# design.net
KiCad netlist of a schematic drawn in Altium Designer
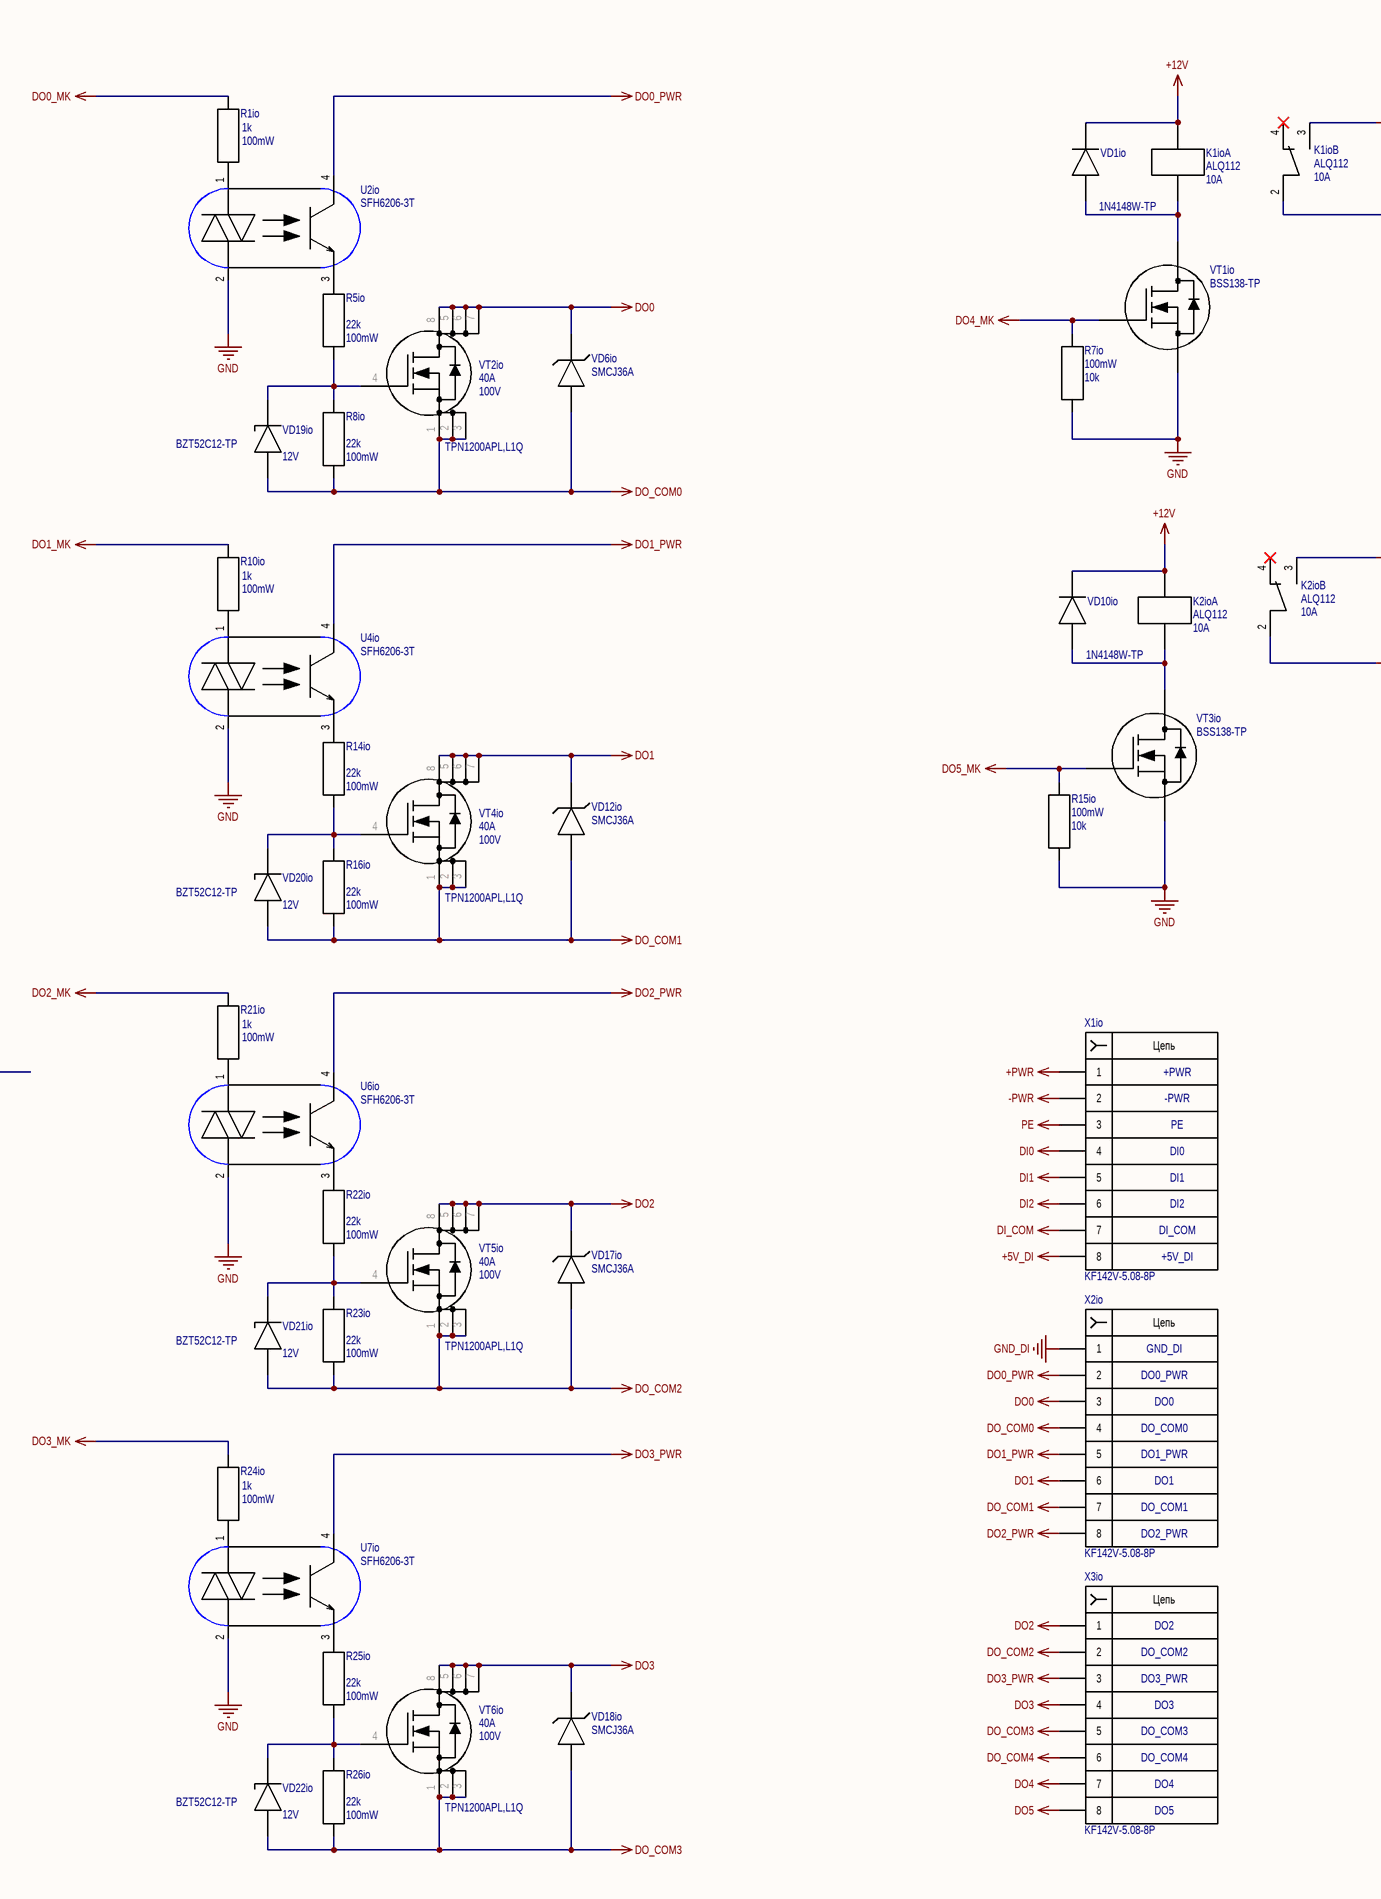
[diagram p0: Схема дискретных входов и выходов.SchDoc, left]
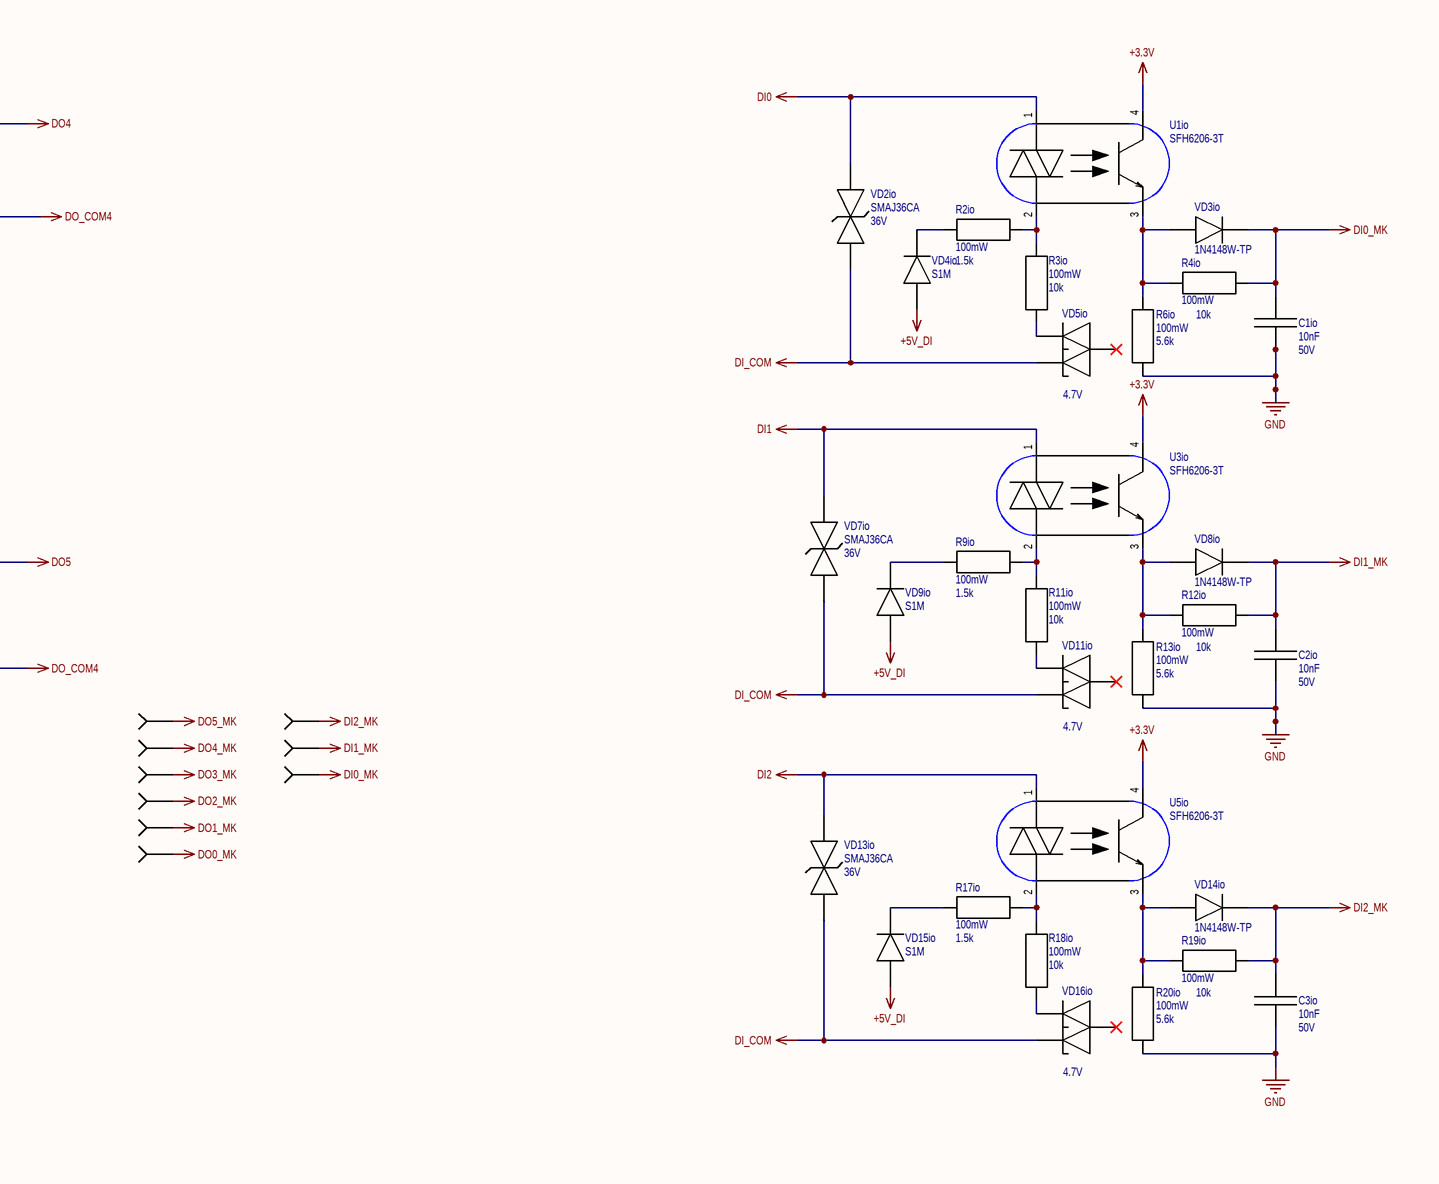
[diagram p1: Схема дискретных входов и выходов.SchDoc, right]

(export (version "E")
  (design (tool "Eeschema 10.0.6"))
  (components
    (comp (ref "C1io")
      (value "CL10B103KB8NNNC")
      (footprint "CAP 0603 IPC MAX")
      (description "CAP SMD CER 10000PF 50V X7R 0603")
      (fields
        (field (name "TOLERANCE") "10%")
        (field (name "CAPACITANCE") "10nF")
        (field (name "RATED VOLTAGE") "50V")
      )
      (libsource (lib "Passive components") (part "CL10B103KB8NNNC"))
    )
    (comp (ref "C2io")
      (value "CL10B103KB8NNNC")
      (footprint "CAP 0603 IPC MAX")
      (description "CAP SMD CER 10000PF 50V X7R 0603")
      (fields
        (field (name "TOLERANCE") "10%")
        (field (name "CAPACITANCE") "10nF")
        (field (name "RATED VOLTAGE") "50V")
      )
      (libsource (lib "Passive components") (part "CL10B103KB8NNNC"))
    )
    (comp (ref "C3io")
      (value "CL10B103KB8NNNC")
      (footprint "CAP 0603 IPC MAX")
      (description "CAP SMD CER 10000PF 50V X7R 0603")
      (fields
        (field (name "TOLERANCE") "10%")
        (field (name "CAPACITANCE") "10nF")
        (field (name "RATED VOLTAGE") "50V")
      )
      (libsource (lib "Passive components") (part "CL10B103KB8NNNC"))
    )
    (comp (ref "K1io")
      (value "ALQ112")
      (footprint "ALQ112")
      (description "RELAY GEN PURPOSE SPDT 10A 12V")
      (fields (field (name "CONTACT RATING") "10A"))
      (libsource (lib "Electromechanical") (part "ALQ112"))
    )
    (comp (ref "K2io")
      (value "ALQ112")
      (footprint "ALQ112")
      (description "RELAY GEN PURPOSE SPDT 10A 12V")
      (fields (field (name "CONTACT RATING") "10A"))
      (libsource (lib "Electromechanical") (part "ALQ112"))
    )
    (comp (ref "R1io")
      (value "RMCF0603FT1K00")
      (footprint "RES 0603 IPC MAX")
      (description "RES SMD 1K OHM 1% 1/10W 0603")
      (fields
        (field (name "RESISTANCE") "1k")
        (field (name "TOLERANCE") "1%")
        (field (name "RATED POWER") "100mW")
      )
      (libsource (lib "Passive components") (part "RMCF0603FT1K00"))
    )
    (comp (ref "R2io")
      (value "RMCF0603FT1K50")
      (footprint "CAP 0603 IPC MAX")
      (description "RES SMD 1.5K OHM 1% 1/10W 0603")
      (fields
        (field (name "TOLERANCE") "1%")
        (field (name "POWER RATED") "100mW")
        (field (name "RESISTANCE") "1.5k")
      )
      (libsource (lib "Passive components") (part "RMCF0603FT1K50"))
    )
    (comp (ref "R3io")
      (value "RMCF0603JT10K0")
      (footprint "RES 0603 IPC MAX")
      (description "RES SMD 10K OHM 5% 1/10W 0603")
      (fields
        (field (name "TOLERANCE") "5%")
        (field (name "POWER RATED") "100mW")
        (field (name "RESISTANCE") "10k")
      )
      (libsource (lib "Passive components") (part "RMCF0603JT10K0"))
    )
    (comp (ref "R4io")
      (value "RMCF0603JT10K0")
      (footprint "RES 0603 IPC MAX")
      (description "RES SMD 10K OHM 5% 1/10W 0603")
      (fields
        (field (name "TOLERANCE") "5%")
        (field (name "POWER RATED") "100mW")
        (field (name "RESISTANCE") "10k")
      )
      (libsource (lib "Passive components") (part "RMCF0603JT10K0"))
    )
    (comp (ref "R5io")
      (value "RMCF0603FT22K0")
      (footprint "RES 0603 IPC MAX")
      (description "RES SMD 22K OHM 1% 1/10W 0603")
      (fields
        (field (name "TOLERANCE") "1%")
        (field (name "RESISTANCE") "22k")
        (field (name "POWER RATED") "100mW")
      )
      (libsource (lib "Passive components") (part "RMCF0603FT22K0"))
    )
    (comp (ref "R6io")
      (value "RMCF0603FT5K60")
      (footprint "RES 0603 IPC MAX")
      (description "RES SMD 5.6K OHM 1% 1/10W 0603")
      (fields
        (field (name "RESISTANCE") "5.6k")
        (field (name "TOLERANCE") "1%")
        (field (name "RATED POWER") "100mW")
      )
      (libsource (lib "Passive components") (part "RMCF0603FT5K60"))
    )
    (comp (ref "R7io")
      (value "RMCF0603JT10K0")
      (footprint "RES 0603 IPC MAX")
      (description "RES SMD 10K OHM 5% 1/10W 0603")
      (fields
        (field (name "TOLERANCE") "5%")
        (field (name "POWER RATED") "100mW")
        (field (name "RESISTANCE") "10k")
      )
      (libsource (lib "Passive components") (part "RMCF0603JT10K0"))
    )
    (comp (ref "R8io")
      (value "RMCF0603FT22K0")
      (footprint "RES 0603 IPC MAX")
      (description "RES SMD 22K OHM 1% 1/10W 0603")
      (fields
        (field (name "TOLERANCE") "1%")
        (field (name "RESISTANCE") "22k")
        (field (name "POWER RATED") "100mW")
      )
      (libsource (lib "Passive components") (part "RMCF0603FT22K0"))
    )
    (comp (ref "R9io")
      (value "RMCF0603FT1K50")
      (footprint "CAP 0603 IPC MAX")
      (description "RES SMD 1.5K OHM 1% 1/10W 0603")
      (fields
        (field (name "TOLERANCE") "1%")
        (field (name "POWER RATED") "100mW")
        (field (name "RESISTANCE") "1.5k")
      )
      (libsource (lib "Passive components") (part "RMCF0603FT1K50"))
    )
    (comp (ref "R10io")
      (value "RMCF0603FT1K00")
      (footprint "RES 0603 IPC MAX")
      (description "RES SMD 1K OHM 1% 1/10W 0603")
      (fields
        (field (name "RESISTANCE") "1k")
        (field (name "TOLERANCE") "1%")
        (field (name "RATED POWER") "100mW")
      )
      (libsource (lib "Passive components") (part "RMCF0603FT1K00"))
    )
    (comp (ref "R11io")
      (value "RMCF0603JT10K0")
      (footprint "RES 0603 IPC MAX")
      (description "RES SMD 10K OHM 5% 1/10W 0603")
      (fields
        (field (name "TOLERANCE") "5%")
        (field (name "POWER RATED") "100mW")
        (field (name "RESISTANCE") "10k")
      )
      (libsource (lib "Passive components") (part "RMCF0603JT10K0"))
    )
    (comp (ref "R12io")
      (value "RMCF0603JT10K0")
      (footprint "RES 0603 IPC MAX")
      (description "RES SMD 10K OHM 5% 1/10W 0603")
      (fields
        (field (name "TOLERANCE") "5%")
        (field (name "POWER RATED") "100mW")
        (field (name "RESISTANCE") "10k")
      )
      (libsource (lib "Passive components") (part "RMCF0603JT10K0"))
    )
    (comp (ref "R13io")
      (value "RMCF0603FT5K60")
      (footprint "RES 0603 IPC MAX")
      (description "RES SMD 5.6K OHM 1% 1/10W 0603")
      (fields
        (field (name "RESISTANCE") "5.6k")
        (field (name "TOLERANCE") "1%")
        (field (name "RATED POWER") "100mW")
      )
      (libsource (lib "Passive components") (part "RMCF0603FT5K60"))
    )
    (comp (ref "R14io")
      (value "RMCF0603FT22K0")
      (footprint "RES 0603 IPC MAX")
      (description "RES SMD 22K OHM 1% 1/10W 0603")
      (fields
        (field (name "TOLERANCE") "1%")
        (field (name "RESISTANCE") "22k")
        (field (name "POWER RATED") "100mW")
      )
      (libsource (lib "Passive components") (part "RMCF0603FT22K0"))
    )
    (comp (ref "R15io")
      (value "RMCF0603JT10K0")
      (footprint "RES 0603 IPC MAX")
      (description "RES SMD 10K OHM 5% 1/10W 0603")
      (fields
        (field (name "TOLERANCE") "5%")
        (field (name "POWER RATED") "100mW")
        (field (name "RESISTANCE") "10k")
      )
      (libsource (lib "Passive components") (part "RMCF0603JT10K0"))
    )
    (comp (ref "R16io")
      (value "RMCF0603FT22K0")
      (footprint "RES 0603 IPC MAX")
      (description "RES SMD 22K OHM 1% 1/10W 0603")
      (fields
        (field (name "TOLERANCE") "1%")
        (field (name "RESISTANCE") "22k")
        (field (name "POWER RATED") "100mW")
      )
      (libsource (lib "Passive components") (part "RMCF0603FT22K0"))
    )
    (comp (ref "R17io")
      (value "RMCF0603FT1K50")
      (footprint "CAP 0603 IPC MAX")
      (description "RES SMD 1.5K OHM 1% 1/10W 0603")
      (fields
        (field (name "TOLERANCE") "1%")
        (field (name "POWER RATED") "100mW")
        (field (name "RESISTANCE") "1.5k")
      )
      (libsource (lib "Passive components") (part "RMCF0603FT1K50"))
    )
    (comp (ref "R18io")
      (value "RMCF0603JT10K0")
      (footprint "RES 0603 IPC MAX")
      (description "RES SMD 10K OHM 5% 1/10W 0603")
      (fields
        (field (name "TOLERANCE") "5%")
        (field (name "POWER RATED") "100mW")
        (field (name "RESISTANCE") "10k")
      )
      (libsource (lib "Passive components") (part "RMCF0603JT10K0"))
    )
    (comp (ref "R19io")
      (value "RMCF0603JT10K0")
      (footprint "RES 0603 IPC MAX")
      (description "RES SMD 10K OHM 5% 1/10W 0603")
      (fields
        (field (name "TOLERANCE") "5%")
        (field (name "POWER RATED") "100mW")
        (field (name "RESISTANCE") "10k")
      )
      (libsource (lib "Passive components") (part "RMCF0603JT10K0"))
    )
    (comp (ref "R20io")
      (value "RMCF0603FT5K60")
      (footprint "RES 0603 IPC MAX")
      (description "RES SMD 5.6K OHM 1% 1/10W 0603")
      (fields
        (field (name "RESISTANCE") "5.6k")
        (field (name "TOLERANCE") "1%")
        (field (name "RATED POWER") "100mW")
      )
      (libsource (lib "Passive components") (part "RMCF0603FT5K60"))
    )
    (comp (ref "R21io")
      (value "RMCF0603FT1K00")
      (footprint "RES 0603 IPC MAX")
      (description "RES SMD 1K OHM 1% 1/10W 0603")
      (fields
        (field (name "RESISTANCE") "1k")
        (field (name "TOLERANCE") "1%")
        (field (name "RATED POWER") "100mW")
      )
      (libsource (lib "Passive components") (part "RMCF0603FT1K00"))
    )
    (comp (ref "R22io")
      (value "RMCF0603FT22K0")
      (footprint "RES 0603 IPC MAX")
      (description "RES SMD 22K OHM 1% 1/10W 0603")
      (fields
        (field (name "TOLERANCE") "1%")
        (field (name "RESISTANCE") "22k")
        (field (name "POWER RATED") "100mW")
      )
      (libsource (lib "Passive components") (part "RMCF0603FT22K0"))
    )
    (comp (ref "R23io")
      (value "RMCF0603FT22K0")
      (footprint "RES 0603 IPC MAX")
      (description "RES SMD 22K OHM 1% 1/10W 0603")
      (fields
        (field (name "TOLERANCE") "1%")
        (field (name "RESISTANCE") "22k")
        (field (name "POWER RATED") "100mW")
      )
      (libsource (lib "Passive components") (part "RMCF0603FT22K0"))
    )
    (comp (ref "R24io")
      (value "RMCF0603FT1K00")
      (footprint "RES 0603 IPC MAX")
      (description "RES SMD 1K OHM 1% 1/10W 0603")
      (fields
        (field (name "RESISTANCE") "1k")
        (field (name "TOLERANCE") "1%")
        (field (name "RATED POWER") "100mW")
      )
      (libsource (lib "Passive components") (part "RMCF0603FT1K00"))
    )
    (comp (ref "R25io")
      (value "RMCF0603FT22K0")
      (footprint "RES 0603 IPC MAX")
      (description "RES SMD 22K OHM 1% 1/10W 0603")
      (fields
        (field (name "TOLERANCE") "1%")
        (field (name "RESISTANCE") "22k")
        (field (name "POWER RATED") "100mW")
      )
      (libsource (lib "Passive components") (part "RMCF0603FT22K0"))
    )
    (comp (ref "R26io")
      (value "RMCF0603FT22K0")
      (footprint "RES 0603 IPC MAX")
      (description "RES SMD 22K OHM 1% 1/10W 0603")
      (fields
        (field (name "TOLERANCE") "1%")
        (field (name "RESISTANCE") "22k")
        (field (name "POWER RATED") "100mW")
      )
      (libsource (lib "Passive components") (part "RMCF0603FT22K0"))
    )
    (comp (ref "TP1io")
      (value "1.2MM TP")
      (footprint "TESTPOINT 1.2mm")
      (libsource (lib "Connectors") (part "Testpoint 1.2mm"))
    )
    (comp (ref "TP2io")
      (value "1.2MM TP")
      (footprint "TESTPOINT 1.2mm")
      (libsource (lib "Connectors") (part "Testpoint 1.2mm"))
    )
    (comp (ref "TP3io")
      (value "1.2MM TP")
      (footprint "TESTPOINT 1.2mm")
      (libsource (lib "Connectors") (part "Testpoint 1.2mm"))
    )
    (comp (ref "TP4io")
      (value "1.2MM TP")
      (footprint "TESTPOINT 1.2mm")
      (libsource (lib "Connectors") (part "Testpoint 1.2mm"))
    )
    (comp (ref "TP5io")
      (value "1.2MM TP")
      (footprint "TESTPOINT 1.2mm")
      (libsource (lib "Connectors") (part "Testpoint 1.2mm"))
    )
    (comp (ref "TP6io")
      (value "1.2MM TP")
      (footprint "TESTPOINT 1.2mm")
      (libsource (lib "Connectors") (part "Testpoint 1.2mm"))
    )
    (comp (ref "TP7io")
      (value "1.2MM TP")
      (footprint "TESTPOINT 1.2mm")
      (libsource (lib "Connectors") (part "Testpoint 1.2mm"))
    )
    (comp (ref "TP9io")
      (value "1.2MM TP")
      (footprint "TESTPOINT 1.2mm")
      (libsource (lib "Connectors") (part "Testpoint 1.2mm"))
    )
    (comp (ref "TP11io")
      (value "1.2MM TP")
      (footprint "TESTPOINT 1.2mm")
      (libsource (lib "Connectors") (part "Testpoint 1.2mm"))
    )
    (comp (ref "U1io")
      (value "SFH6206-3T")
      (footprint "11-5L106")
      (description "OPTOISOLATOR 5.3KV TRANS 4-SMD")
      (libsource (lib "Optos") (part "SFH6206-3T"))
    )
    (comp (ref "U2io")
      (value "SFH6206-3T")
      (footprint "11-5L106")
      (description "OPTOISOLATOR 5.3KV TRANS 4-SMD")
      (libsource (lib "Optos") (part "SFH6206-3T"))
    )
    (comp (ref "U3io")
      (value "SFH6206-3T")
      (footprint "11-5L106")
      (description "OPTOISOLATOR 5.3KV TRANS 4-SMD")
      (libsource (lib "Optos") (part "SFH6206-3T"))
    )
    (comp (ref "U4io")
      (value "SFH6206-3T")
      (footprint "11-5L106")
      (description "OPTOISOLATOR 5.3KV TRANS 4-SMD")
      (libsource (lib "Optos") (part "SFH6206-3T"))
    )
    (comp (ref "U5io")
      (value "SFH6206-3T")
      (footprint "11-5L106")
      (description "OPTOISOLATOR 5.3KV TRANS 4-SMD")
      (libsource (lib "Optos") (part "SFH6206-3T"))
    )
    (comp (ref "U6io")
      (value "SFH6206-3T")
      (footprint "11-5L106")
      (description "OPTOISOLATOR 5.3KV TRANS 4-SMD")
      (libsource (lib "Optos") (part "SFH6206-3T"))
    )
    (comp (ref "U7io")
      (value "SFH6206-3T")
      (footprint "11-5L106")
      (description "OPTOISOLATOR 5.3KV TRANS 4-SMD")
      (libsource (lib "Optos") (part "SFH6206-3T"))
    )
    (comp (ref "VD1io")
      (value "1N4148W-TP")
      (footprint "SOD-123 (Marked)")
      (description "DIODE GEN PURP 100V 150MA SOD123")
      (libsource (lib "Diodes") (part "1N4148W-TP"))
    )
    (comp (ref "VD2io")
      (value "SMAJ36CA")
      (footprint "DO-214AC Bidirectional")
      (description "TVS DIODE 36VWM 58.1VC DO214AC")
      (fields (field (name "VOLTAGE - REVERSE STANDOFF (TYP)") "36V"))
      (libsource (lib "Diodes") (part "SMAJ36CA"))
    )
    (comp (ref "VD3io")
      (value "1N4148W-TP")
      (footprint "SOD-123 (Marked)")
      (description "DIODE GEN PURP 100V 150MA SOD123")
      (libsource (lib "Diodes") (part "1N4148W-TP"))
    )
    (comp (ref "VD4io")
      (value "S1M")
      (footprint "DO-214AC Unidirectional")
      (description "DIODE GEN PURP 1KV 1A SMA")
      (libsource (lib "Diodes") (part "S1M"))
    )
    (comp (ref "VD5io")
      (value "AZ23C4V7-HE3-08")
      (footprint "SOT-23-3")
      (description "DIODE ZENER ARRAY 4.7V 300MW SOT23")
      (fields (field (name "ZENER VOLTAGE") "4.7V") (field (name "TOLERANCE") "5%"))
      (libsource (lib "Diodes") (part "AZ23C4V7-HE3-08"))
    )
    (comp (ref "VD6io")
      (value "SMCJ36A")
      (footprint "DO214-AB (SMC) L3.2W1.52")
      (description "TVS DIODE 36VWM 58.1VC DO214AB")
      (libsource (lib "Diodes") (part "SMCJ36A"))
    )
    (comp (ref "VD7io")
      (value "SMAJ36CA")
      (footprint "DO-214AC Bidirectional")
      (description "TVS DIODE 36VWM 58.1VC DO214AC")
      (fields (field (name "VOLTAGE - REVERSE STANDOFF (TYP)") "36V"))
      (libsource (lib "Diodes") (part "SMAJ36CA"))
    )
    (comp (ref "VD8io")
      (value "1N4148W-TP")
      (footprint "SOD-123 (Marked)")
      (description "DIODE GEN PURP 100V 150MA SOD123")
      (libsource (lib "Diodes") (part "1N4148W-TP"))
    )
    (comp (ref "VD9io")
      (value "S1M")
      (footprint "DO-214AC Unidirectional")
      (description "DIODE GEN PURP 1KV 1A SMA")
      (libsource (lib "Diodes") (part "S1M"))
    )
    (comp (ref "VD10io")
      (value "1N4148W-TP")
      (footprint "SOD-123 (Marked)")
      (description "DIODE GEN PURP 100V 150MA SOD123")
      (libsource (lib "Diodes") (part "1N4148W-TP"))
    )
    (comp (ref "VD11io")
      (value "AZ23C4V7-HE3-08")
      (footprint "SOT-23-3")
      (description "DIODE ZENER ARRAY 4.7V 300MW SOT23")
      (fields (field (name "ZENER VOLTAGE") "4.7V") (field (name "TOLERANCE") "5%"))
      (libsource (lib "Diodes") (part "AZ23C4V7-HE3-08"))
    )
    (comp (ref "VD12io")
      (value "SMCJ36A")
      (footprint "DO214-AB (SMC) L3.2W1.52")
      (description "TVS DIODE 36VWM 58.1VC DO214AB")
      (libsource (lib "Diodes") (part "SMCJ36A"))
    )
    (comp (ref "VD13io")
      (value "SMAJ36CA")
      (footprint "DO-214AC Bidirectional")
      (description "TVS DIODE 36VWM 58.1VC DO214AC")
      (fields (field (name "VOLTAGE - REVERSE STANDOFF (TYP)") "36V"))
      (libsource (lib "Diodes") (part "SMAJ36CA"))
    )
    (comp (ref "VD14io")
      (value "1N4148W-TP")
      (footprint "SOD-123 (Marked)")
      (description "DIODE GEN PURP 100V 150MA SOD123")
      (libsource (lib "Diodes") (part "1N4148W-TP"))
    )
    (comp (ref "VD15io")
      (value "S1M")
      (footprint "DO-214AC Unidirectional")
      (description "DIODE GEN PURP 1KV 1A SMA")
      (libsource (lib "Diodes") (part "S1M"))
    )
    (comp (ref "VD16io")
      (value "AZ23C4V7-HE3-08")
      (footprint "SOT-23-3")
      (description "DIODE ZENER ARRAY 4.7V 300MW SOT23")
      (fields (field (name "ZENER VOLTAGE") "4.7V") (field (name "TOLERANCE") "5%"))
      (libsource (lib "Diodes") (part "AZ23C4V7-HE3-08"))
    )
    (comp (ref "VD17io")
      (value "SMCJ36A")
      (footprint "DO214-AB (SMC) L3.2W1.52")
      (description "TVS DIODE 36VWM 58.1VC DO214AB")
      (libsource (lib "Diodes") (part "SMCJ36A"))
    )
    (comp (ref "VD18io")
      (value "SMCJ36A")
      (footprint "DO214-AB (SMC) L3.2W1.52")
      (description "TVS DIODE 36VWM 58.1VC DO214AB")
      (libsource (lib "Diodes") (part "SMCJ36A"))
    )
    (comp (ref "VD19io")
      (value "BZT52C12-TP")
      (footprint "SOD-123 (Marked)")
      (description "DIODE ZENER 12V 200MW SOD123")
      (fields (field (name "TOLERANCE") "5%") (field (name "ZENER VOLTAGE") "12V"))
      (libsource (lib "Diodes") (part "BZT52C12-TP"))
    )
    (comp (ref "VD20io")
      (value "BZT52C12-TP")
      (footprint "SOD-123 (Marked)")
      (description "DIODE ZENER 12V 200MW SOD123")
      (fields (field (name "TOLERANCE") "5%") (field (name "ZENER VOLTAGE") "12V"))
      (libsource (lib "Diodes") (part "BZT52C12-TP"))
    )
    (comp (ref "VD21io")
      (value "BZT52C12-TP")
      (footprint "SOD-123 (Marked)")
      (description "DIODE ZENER 12V 200MW SOD123")
      (fields (field (name "TOLERANCE") "5%") (field (name "ZENER VOLTAGE") "12V"))
      (libsource (lib "Diodes") (part "BZT52C12-TP"))
    )
    (comp (ref "VD22io")
      (value "BZT52C12-TP")
      (footprint "SOD-123 (Marked)")
      (description "DIODE ZENER 12V 200MW SOD123")
      (fields (field (name "TOLERANCE") "5%") (field (name "ZENER VOLTAGE") "12V"))
      (libsource (lib "Diodes") (part "BZT52C12-TP"))
    )
    (comp (ref "VT1io")
      (value "BSS138-TP")
      (footprint "SOT-23-3")
      (description "MOSFET N-CH 50V 220MA SOT23")
      (libsource (lib "MOSFET") (part "BSS138-TP"))
    )
    (comp (ref "VT2io")
      (value "TPN1200APL,L1Q")
      (footprint "8-PowerVDFN")
      (description "MOSFET N-CH 100V 42A MLPAK33")
      (fields (field (name "MAX DRAIN CURRENT") "40A") (field (name "VDS MAX") "100V"))
      (libsource (lib "MOSFET") (part "TPN1200APL,L1Q"))
    )
    (comp (ref "VT3io")
      (value "BSS138-TP")
      (footprint "SOT-23-3")
      (description "MOSFET N-CH 50V 220MA SOT23")
      (libsource (lib "MOSFET") (part "BSS138-TP"))
    )
    (comp (ref "VT4io")
      (value "TPN1200APL,L1Q")
      (footprint "8-PowerVDFN")
      (description "MOSFET N-CH 100V 42A MLPAK33")
      (fields (field (name "MAX DRAIN CURRENT") "40A") (field (name "VDS MAX") "100V"))
      (libsource (lib "MOSFET") (part "TPN1200APL,L1Q"))
    )
    (comp (ref "VT5io")
      (value "TPN1200APL,L1Q")
      (footprint "8-PowerVDFN")
      (description "MOSFET N-CH 100V 42A MLPAK33")
      (fields (field (name "MAX DRAIN CURRENT") "40A") (field (name "VDS MAX") "100V"))
      (libsource (lib "MOSFET") (part "TPN1200APL,L1Q"))
    )
    (comp (ref "VT6io")
      (value "TPN1200APL,L1Q")
      (footprint "8-PowerVDFN")
      (description "MOSFET N-CH 100V 42A MLPAK33")
      (fields (field (name "MAX DRAIN CURRENT") "40A") (field (name "VDS MAX") "100V"))
      (libsource (lib "MOSFET") (part "TPN1200APL,L1Q"))
    )
    (comp (ref "X1io")
      (value "KF142V-5.08-8P")
      (footprint "KF142V-5.08-8P")
      (description "TERMINAL BLOCK 8 PIN 5.08mm 15A 250V T/H")
      (libsource (lib "Connectors") (part "KF142V-5.08-8P"))
    )
    (comp (ref "X2io")
      (value "KF142V-5.08-8P")
      (footprint "KF142V-5.08-8P")
      (description "TERMINAL BLOCK 8 PIN 5.08mm 15A 250V T/H")
      (libsource (lib "Connectors") (part "KF142V-5.08-8P"))
    )
    (comp (ref "X3io")
      (value "KF142V-5.08-8P")
      (footprint "KF142V-5.08-8P")
      (description "TERMINAL BLOCK 8 PIN 5.08mm 15A 250V T/H")
      (libsource (lib "Connectors") (part "KF142V-5.08-8P"))
    )
  )
  (nets
    (net (code "1") (name "+3.3V") (class "Default")
      (node (ref "U1io") (pin "4") (pinfunction "Collector_4") (pintype "passive"))
      (node (ref "U3io") (pin "4") (pinfunction "Collector_4") (pintype "passive"))
      (node (ref "U5io") (pin "4") (pinfunction "Collector_4") (pintype "passive"))
    )
    (net (code "2") (name "+5V_DI") (class "Default")
      (node (ref "VD15io") (pin "2") (pinfunction "2_2") (pintype "passive"))
      (node (ref "VD4io") (pin "2") (pinfunction "2_2") (pintype "passive"))
      (node (ref "VD9io") (pin "2") (pinfunction "2_2") (pintype "passive"))
      (node (ref "X1io") (pin "8") (pinfunction "8_8") (pintype "passive"))
    )
    (net (code "3") (name "+12V") (class "Default")
      (node (ref "K1io") (pin "1") (pinfunction "1_1") (pintype "passive"))
      (node (ref "K2io") (pin "1") (pinfunction "1_1") (pintype "passive"))
      (node (ref "VD10io") (pin "1") (pinfunction "1_1") (pintype "passive"))
      (node (ref "VD1io") (pin "1") (pinfunction "1_1") (pintype "passive"))
    )
    (net (code "4") (name "+PWR") (class "Default")
      (node (ref "X1io") (pin "1") (pinfunction "1_1") (pintype "passive"))
    )
    (net (code "5") (name "-PWR") (class "Default")
      (node (ref "X1io") (pin "2") (pinfunction "2_2") (pintype "passive"))
    )
    (net (code "7") (name "DI0") (class "Default")
      (node (ref "U1io") (pin "1") (pinfunction "1_1") (pintype "passive"))
      (node (ref "VD2io") (pin "2") (pinfunction "2_2") (pintype "passive"))
      (node (ref "X1io") (pin "4") (pinfunction "4_4") (pintype "passive"))
    )
    (net (code "8") (name "DI0_MK") (class "Default")
      (node (ref "C1io") (pin "1") (pinfunction "1_1") (pintype "passive"))
      (node (ref "R4io") (pin "1") (pinfunction "1_1") (pintype "passive"))
      (node (ref "TP6io") (pin "1") (pinfunction "1_1") (pintype "passive"))
      (node (ref "VD3io") (pin "1") (pinfunction "1_1") (pintype "passive"))
    )
    (net (code "9") (name "DI1") (class "Default")
      (node (ref "U3io") (pin "1") (pinfunction "1_1") (pintype "passive"))
      (node (ref "VD7io") (pin "2") (pinfunction "2_2") (pintype "passive"))
      (node (ref "X1io") (pin "5") (pinfunction "5_5") (pintype "passive"))
    )
    (net (code "10") (name "DI1_MK") (class "Default")
      (node (ref "C2io") (pin "1") (pinfunction "1_1") (pintype "passive"))
      (node (ref "R12io") (pin "1") (pinfunction "1_1") (pintype "passive"))
      (node (ref "TP4io") (pin "1") (pinfunction "1_1") (pintype "passive"))
      (node (ref "VD8io") (pin "1") (pinfunction "1_1") (pintype "passive"))
    )
    (net (code "11") (name "DI2") (class "Default")
      (node (ref "U5io") (pin "1") (pinfunction "1_1") (pintype "passive"))
      (node (ref "VD13io") (pin "2") (pinfunction "2_2") (pintype "passive"))
      (node (ref "X1io") (pin "6") (pinfunction "6_6") (pintype "passive"))
    )
    (net (code "12") (name "DI2_MK") (class "Default")
      (node (ref "C3io") (pin "1") (pinfunction "1_1") (pintype "passive"))
      (node (ref "R19io") (pin "1") (pinfunction "1_1") (pintype "passive"))
      (node (ref "TP2io") (pin "1") (pinfunction "1_1") (pintype "passive"))
      (node (ref "VD14io") (pin "1") (pinfunction "1_1") (pintype "passive"))
    )
    (net (code "13") (name "DI_COM") (class "Default")
      (node (ref "VD11io") (pin "2") (pinfunction "2_2") (pintype "passive"))
      (node (ref "VD13io") (pin "1") (pinfunction "1_1") (pintype "passive"))
      (node (ref "VD16io") (pin "2") (pinfunction "2_2") (pintype "passive"))
      (node (ref "VD2io") (pin "1") (pinfunction "1_1") (pintype "passive"))
      (node (ref "VD5io") (pin "2") (pinfunction "2_2") (pintype "passive"))
      (node (ref "VD7io") (pin "1") (pinfunction "1_1") (pintype "passive"))
      (node (ref "X1io") (pin "7") (pinfunction "7_7") (pintype "passive"))
    )
    (net (code "14") (name "DO0") (class "Default")
      (node (ref "VD6io") (pin "2") (pinfunction "2_2") (pintype "passive"))
      (node (ref "VT2io") (pin "5") (pinfunction "5_5") (pintype "passive"))
      (node (ref "VT2io") (pin "6") (pinfunction "6_6") (pintype "passive"))
      (node (ref "VT2io") (pin "7") (pinfunction "7_7") (pintype "passive"))
      (node (ref "VT2io") (pin "8") (pinfunction "D_8") (pintype "passive"))
      (node (ref "X2io") (pin "3") (pinfunction "3_3") (pintype "passive"))
    )
    (net (code "15") (name "DO0_MK") (class "Default")
      (node (ref "R1io") (pin "1") (pinfunction "1_1") (pintype "passive"))
      (node (ref "TP11io") (pin "1") (pinfunction "1_1") (pintype "passive"))
    )
    (net (code "16") (name "DO0_PWR") (class "Default")
      (node (ref "U2io") (pin "4") (pinfunction "Collector_4") (pintype "passive"))
      (node (ref "X2io") (pin "2") (pinfunction "2_2") (pintype "passive"))
    )
    (net (code "17") (name "DO1") (class "Default")
      (node (ref "VD12io") (pin "2") (pinfunction "2_2") (pintype "passive"))
      (node (ref "VT4io") (pin "5") (pinfunction "5_5") (pintype "passive"))
      (node (ref "VT4io") (pin "6") (pinfunction "6_6") (pintype "passive"))
      (node (ref "VT4io") (pin "7") (pinfunction "7_7") (pintype "passive"))
      (node (ref "VT4io") (pin "8") (pinfunction "D_8") (pintype "passive"))
      (node (ref "X2io") (pin "6") (pinfunction "6_6") (pintype "passive"))
    )
    (net (code "18") (name "DO1_MK") (class "Default")
      (node (ref "R10io") (pin "1") (pinfunction "1_1") (pintype "passive"))
      (node (ref "TP9io") (pin "1") (pinfunction "1_1") (pintype "passive"))
    )
    (net (code "19") (name "DO1_PWR") (class "Default")
      (node (ref "U4io") (pin "4") (pinfunction "Collector_4") (pintype "passive"))
      (node (ref "X2io") (pin "5") (pinfunction "5_5") (pintype "passive"))
    )
    (net (code "20") (name "DO2") (class "Default")
      (node (ref "VD17io") (pin "2") (pinfunction "2_2") (pintype "passive"))
      (node (ref "VT5io") (pin "5") (pinfunction "5_5") (pintype "passive"))
      (node (ref "VT5io") (pin "6") (pinfunction "6_6") (pintype "passive"))
      (node (ref "VT5io") (pin "7") (pinfunction "7_7") (pintype "passive"))
      (node (ref "VT5io") (pin "8") (pinfunction "D_8") (pintype "passive"))
      (node (ref "X3io") (pin "1") (pinfunction "1_1") (pintype "passive"))
    )
    (net (code "21") (name "DO2_MK") (class "Default")
      (node (ref "R21io") (pin "1") (pinfunction "1_1") (pintype "passive"))
      (node (ref "TP7io") (pin "1") (pinfunction "1_1") (pintype "passive"))
    )
    (net (code "22") (name "DO2_PWR") (class "Default")
      (node (ref "U6io") (pin "4") (pinfunction "Collector_4") (pintype "passive"))
      (node (ref "X2io") (pin "8") (pinfunction "8_8") (pintype "passive"))
    )
    (net (code "23") (name "DO3") (class "Default")
      (node (ref "VD18io") (pin "2") (pinfunction "2_2") (pintype "passive"))
      (node (ref "VT6io") (pin "5") (pinfunction "5_5") (pintype "passive"))
      (node (ref "VT6io") (pin "6") (pinfunction "6_6") (pintype "passive"))
      (node (ref "VT6io") (pin "7") (pinfunction "7_7") (pintype "passive"))
      (node (ref "VT6io") (pin "8") (pinfunction "D_8") (pintype "passive"))
      (node (ref "X3io") (pin "4") (pinfunction "4_4") (pintype "passive"))
    )
    (net (code "24") (name "DO3_MK") (class "Default")
      (node (ref "R24io") (pin "1") (pinfunction "1_1") (pintype "passive"))
      (node (ref "TP5io") (pin "1") (pinfunction "1_1") (pintype "passive"))
    )
    (net (code "25") (name "DO3_PWR") (class "Default")
      (node (ref "U7io") (pin "4") (pinfunction "Collector_4") (pintype "passive"))
      (node (ref "X3io") (pin "3") (pinfunction "3_3") (pintype "passive"))
    )
    (net (code "26") (name "DO4") (class "Default")
      (node (ref "K1io") (pin "3") (pinfunction "3_3") (pintype "passive"))
      (node (ref "X3io") (pin "7") (pinfunction "7_7") (pintype "passive"))
    )
    (net (code "27") (name "DO4_MK") (class "Default")
      (node (ref "R7io") (pin "2") (pinfunction "2_2") (pintype "passive"))
      (node (ref "TP3io") (pin "1") (pinfunction "1_1") (pintype "passive"))
      (node (ref "VT1io") (pin "1") (pinfunction "G_1") (pintype "passive"))
    )
    (net (code "28") (name "DO5") (class "Default")
      (node (ref "K2io") (pin "3") (pinfunction "3_3") (pintype "passive"))
      (node (ref "X3io") (pin "8") (pinfunction "8_8") (pintype "passive"))
    )
    (net (code "29") (name "DO5_MK") (class "Default")
      (node (ref "R15io") (pin "2") (pinfunction "2_2") (pintype "passive"))
      (node (ref "TP1io") (pin "1") (pinfunction "1_1") (pintype "passive"))
      (node (ref "VT3io") (pin "1") (pinfunction "G_1") (pintype "passive"))
    )
    (net (code "30") (name "DO_COM0") (class "Default")
      (node (ref "R8io") (pin "1") (pinfunction "1_1") (pintype "passive"))
      (node (ref "VD19io") (pin "2") (pinfunction "2_2") (pintype "passive"))
      (node (ref "VD6io") (pin "1") (pinfunction "1_1") (pintype "passive"))
      (node (ref "VT2io") (pin "1") (pinfunction "S_1") (pintype "passive"))
      (node (ref "VT2io") (pin "2") (pinfunction "S_2") (pintype "passive"))
      (node (ref "VT2io") (pin "3") (pinfunction "S_3") (pintype "passive"))
      (node (ref "X2io") (pin "4") (pinfunction "4_4") (pintype "passive"))
    )
    (net (code "31") (name "DO_COM1") (class "Default")
      (node (ref "R16io") (pin "1") (pinfunction "1_1") (pintype "passive"))
      (node (ref "VD12io") (pin "1") (pinfunction "1_1") (pintype "passive"))
      (node (ref "VD20io") (pin "2") (pinfunction "2_2") (pintype "passive"))
      (node (ref "VT4io") (pin "1") (pinfunction "S_1") (pintype "passive"))
      (node (ref "VT4io") (pin "2") (pinfunction "S_2") (pintype "passive"))
      (node (ref "VT4io") (pin "3") (pinfunction "S_3") (pintype "passive"))
      (node (ref "X2io") (pin "7") (pinfunction "7_7") (pintype "passive"))
    )
    (net (code "32") (name "DO_COM2") (class "Default")
      (node (ref "R23io") (pin "1") (pinfunction "1_1") (pintype "passive"))
      (node (ref "VD17io") (pin "1") (pinfunction "1_1") (pintype "passive"))
      (node (ref "VD21io") (pin "2") (pinfunction "2_2") (pintype "passive"))
      (node (ref "VT5io") (pin "1") (pinfunction "S_1") (pintype "passive"))
      (node (ref "VT5io") (pin "2") (pinfunction "S_2") (pintype "passive"))
      (node (ref "VT5io") (pin "3") (pinfunction "S_3") (pintype "passive"))
      (node (ref "X3io") (pin "2") (pinfunction "2_2") (pintype "passive"))
    )
    (net (code "33") (name "DO_COM3") (class "Default")
      (node (ref "R26io") (pin "1") (pinfunction "1_1") (pintype "passive"))
      (node (ref "VD18io") (pin "1") (pinfunction "1_1") (pintype "passive"))
      (node (ref "VD22io") (pin "2") (pinfunction "2_2") (pintype "passive"))
      (node (ref "VT6io") (pin "1") (pinfunction "S_1") (pintype "passive"))
      (node (ref "VT6io") (pin "2") (pinfunction "S_2") (pintype "passive"))
      (node (ref "VT6io") (pin "3") (pinfunction "S_3") (pintype "passive"))
      (node (ref "X3io") (pin "5") (pinfunction "5_5") (pintype "passive"))
    )
    (net (code "34") (name "DO_COM4") (class "Default")
      (node (ref "K1io") (pin "2") (pinfunction "2_2") (pintype "passive"))
      (node (ref "K2io") (pin "2") (pinfunction "2_2") (pintype "passive"))
      (node (ref "X3io") (pin "6") (pinfunction "6_6") (pintype "passive"))
    )
    (net (code "35") (name "GND") (class "Default")
      (node (ref "C1io") (pin "2") (pinfunction "2_2") (pintype "passive"))
      (node (ref "C2io") (pin "2") (pinfunction "2_2") (pintype "passive"))
      (node (ref "C3io") (pin "2") (pinfunction "2_2") (pintype "passive"))
      (node (ref "R13io") (pin "1") (pinfunction "1_1") (pintype "passive"))
      (node (ref "R15io") (pin "1") (pinfunction "1_1") (pintype "passive"))
      (node (ref "R20io") (pin "1") (pinfunction "1_1") (pintype "passive"))
      (node (ref "R6io") (pin "1") (pinfunction "1_1") (pintype "passive"))
      (node (ref "R7io") (pin "1") (pinfunction "1_1") (pintype "passive"))
      (node (ref "U2io") (pin "2") (pinfunction "2_2") (pintype "passive"))
      (node (ref "U4io") (pin "2") (pinfunction "2_2") (pintype "passive"))
      (node (ref "U6io") (pin "2") (pinfunction "2_2") (pintype "passive"))
      (node (ref "U7io") (pin "2") (pinfunction "2_2") (pintype "passive"))
      (node (ref "VT1io") (pin "2") (pinfunction "S_2") (pintype "passive"))
      (node (ref "VT3io") (pin "2") (pinfunction "S_2") (pintype "passive"))
    )
    (net (code "36") (name "GND_DI") (class "Default")
      (node (ref "X2io") (pin "1") (pinfunction "1_1") (pintype "passive"))
    )
    (net (code "37") (name "Net-(R1io-Pad2)") (class "Default")
      (node (ref "R1io") (pin "2") (pinfunction "2_2") (pintype "passive"))
      (node (ref "U2io") (pin "1") (pinfunction "1_1") (pintype "passive"))
    )
    (net (code "38") (name "Net-(R2io-Pad1)") (class "Default")
      (node (ref "R2io") (pin "1") (pinfunction "1_1") (pintype "passive"))
      (node (ref "VD4io") (pin "1") (pinfunction "1_1") (pintype "passive"))
    )
    (net (code "39") (name "Net-(R2io-Pad2)") (class "Default")
      (node (ref "R2io") (pin "2") (pinfunction "2_2") (pintype "passive"))
      (node (ref "R3io") (pin "2") (pinfunction "2_2") (pintype "passive"))
      (node (ref "U1io") (pin "2") (pinfunction "2_2") (pintype "passive"))
    )
    (net (code "40") (name "Net-(R3io-Pad1)") (class "Default")
      (node (ref "R3io") (pin "1") (pinfunction "1_1") (pintype "passive"))
      (node (ref "VD5io") (pin "1") (pinfunction "1_1") (pintype "passive"))
    )
    (net (code "41") (name "Net-(R9io-Pad1)") (class "Default")
      (node (ref "R9io") (pin "1") (pinfunction "1_1") (pintype "passive"))
      (node (ref "VD9io") (pin "1") (pinfunction "1_1") (pintype "passive"))
    )
    (net (code "42") (name "Net-(R10io-Pad2)") (class "Default")
      (node (ref "R10io") (pin "2") (pinfunction "2_2") (pintype "passive"))
      (node (ref "U4io") (pin "1") (pinfunction "1_1") (pintype "passive"))
    )
    (net (code "43") (name "Net-(R11io-Pad1)") (class "Default")
      (node (ref "R11io") (pin "1") (pinfunction "1_1") (pintype "passive"))
      (node (ref "VD11io") (pin "1") (pinfunction "1_1") (pintype "passive"))
    )
    (net (code "44") (name "Net-(R11io-Pad2)") (class "Default")
      (node (ref "R11io") (pin "2") (pinfunction "2_2") (pintype "passive"))
      (node (ref "R9io") (pin "2") (pinfunction "2_2") (pintype "passive"))
      (node (ref "U3io") (pin "2") (pinfunction "2_2") (pintype "passive"))
    )
    (net (code "45") (name "Net-(R17io-Pad1)") (class "Default")
      (node (ref "R17io") (pin "1") (pinfunction "1_1") (pintype "passive"))
      (node (ref "VD15io") (pin "1") (pinfunction "1_1") (pintype "passive"))
    )
    (net (code "46") (name "Net-(R17io-Pad2)") (class "Default")
      (node (ref "R17io") (pin "2") (pinfunction "2_2") (pintype "passive"))
      (node (ref "R18io") (pin "2") (pinfunction "2_2") (pintype "passive"))
      (node (ref "U5io") (pin "2") (pinfunction "2_2") (pintype "passive"))
    )
    (net (code "47") (name "Net-(R18io-Pad1)") (class "Default")
      (node (ref "R18io") (pin "1") (pinfunction "1_1") (pintype "passive"))
      (node (ref "VD16io") (pin "1") (pinfunction "1_1") (pintype "passive"))
    )
    (net (code "48") (name "Net-(R21io-Pad2)") (class "Default")
      (node (ref "R21io") (pin "2") (pinfunction "2_2") (pintype "passive"))
      (node (ref "U6io") (pin "1") (pinfunction "1_1") (pintype "passive"))
    )
    (net (code "49") (name "Net-(R24io-Pad2)") (class "Default")
      (node (ref "R24io") (pin "2") (pinfunction "2_2") (pintype "passive"))
      (node (ref "U7io") (pin "1") (pinfunction "1_1") (pintype "passive"))
    )
    (net (code "50") (name "Net-(U1io-Emitter)") (class "Default")
      (node (ref "R4io") (pin "2") (pinfunction "2_2") (pintype "passive"))
      (node (ref "R6io") (pin "2") (pinfunction "2_2") (pintype "passive"))
      (node (ref "U1io") (pin "3") (pinfunction "Emitter_3") (pintype "passive"))
      (node (ref "VD3io") (pin "2") (pinfunction "2_2") (pintype "passive"))
    )
    (net (code "51") (name "Net-(U2io-Emitter)") (class "Default")
      (node (ref "R5io") (pin "2") (pinfunction "2_2") (pintype "passive"))
      (node (ref "U2io") (pin "3") (pinfunction "Emitter_3") (pintype "passive"))
    )
    (net (code "52") (name "Net-(U3io-Emitter)") (class "Default")
      (node (ref "R12io") (pin "2") (pinfunction "2_2") (pintype "passive"))
      (node (ref "R13io") (pin "2") (pinfunction "2_2") (pintype "passive"))
      (node (ref "U3io") (pin "3") (pinfunction "Emitter_3") (pintype "passive"))
      (node (ref "VD8io") (pin "2") (pinfunction "2_2") (pintype "passive"))
    )
    (net (code "53") (name "Net-(U4io-Emitter)") (class "Default")
      (node (ref "R14io") (pin "2") (pinfunction "2_2") (pintype "passive"))
      (node (ref "U4io") (pin "3") (pinfunction "Emitter_3") (pintype "passive"))
    )
    (net (code "54") (name "Net-(U5io-Emitter)") (class "Default")
      (node (ref "R19io") (pin "2") (pinfunction "2_2") (pintype "passive"))
      (node (ref "R20io") (pin "2") (pinfunction "2_2") (pintype "passive"))
      (node (ref "U5io") (pin "3") (pinfunction "Emitter_3") (pintype "passive"))
      (node (ref "VD14io") (pin "2") (pinfunction "2_2") (pintype "passive"))
    )
    (net (code "55") (name "Net-(U6io-Emitter)") (class "Default")
      (node (ref "R22io") (pin "2") (pinfunction "2_2") (pintype "passive"))
      (node (ref "U6io") (pin "3") (pinfunction "Emitter_3") (pintype "passive"))
    )
    (net (code "56") (name "Net-(U7io-Emitter)") (class "Default")
      (node (ref "R25io") (pin "2") (pinfunction "2_2") (pintype "passive"))
      (node (ref "U7io") (pin "3") (pinfunction "Emitter_3") (pintype "passive"))
    )
    (net (code "57") (name "Net-(VT1io-D)") (class "Default")
      (node (ref "K1io") (pin "5") (pinfunction "5_5") (pintype "passive"))
      (node (ref "VD1io") (pin "2") (pinfunction "2_2") (pintype "passive"))
      (node (ref "VT1io") (pin "3") (pinfunction "D_3") (pintype "passive"))
    )
    (net (code "58") (name "Net-(VT2io-G)") (class "Default")
      (node (ref "R5io") (pin "1") (pinfunction "1_1") (pintype "passive"))
      (node (ref "R8io") (pin "2") (pinfunction "2_2") (pintype "passive"))
      (node (ref "VD19io") (pin "1") (pinfunction "1_1") (pintype "passive"))
      (node (ref "VT2io") (pin "4") (pinfunction "G_4") (pintype "passive"))
    )
    (net (code "59") (name "Net-(VT3io-D)") (class "Default")
      (node (ref "K2io") (pin "5") (pinfunction "5_5") (pintype "passive"))
      (node (ref "VD10io") (pin "2") (pinfunction "2_2") (pintype "passive"))
      (node (ref "VT3io") (pin "3") (pinfunction "D_3") (pintype "passive"))
    )
    (net (code "60") (name "Net-(VT4io-G)") (class "Default")
      (node (ref "R14io") (pin "1") (pinfunction "1_1") (pintype "passive"))
      (node (ref "R16io") (pin "2") (pinfunction "2_2") (pintype "passive"))
      (node (ref "VD20io") (pin "1") (pinfunction "1_1") (pintype "passive"))
      (node (ref "VT4io") (pin "4") (pinfunction "G_4") (pintype "passive"))
    )
    (net (code "61") (name "Net-(VT5io-G)") (class "Default")
      (node (ref "R22io") (pin "1") (pinfunction "1_1") (pintype "passive"))
      (node (ref "R23io") (pin "2") (pinfunction "2_2") (pintype "passive"))
      (node (ref "VD21io") (pin "1") (pinfunction "1_1") (pintype "passive"))
      (node (ref "VT5io") (pin "4") (pinfunction "G_4") (pintype "passive"))
    )
    (net (code "62") (name "Net-(VT6io-G)") (class "Default")
      (node (ref "R25io") (pin "1") (pinfunction "1_1") (pintype "passive"))
      (node (ref "R26io") (pin "2") (pinfunction "2_2") (pintype "passive"))
      (node (ref "VD22io") (pin "1") (pinfunction "1_1") (pintype "passive"))
      (node (ref "VT6io") (pin "4") (pinfunction "G_4") (pintype "passive"))
    )
    (net (code "63") (name "PE") (class "Default")
      (node (ref "X1io") (pin "3") (pinfunction "3_3") (pintype "passive"))
    )
    (net (code "64") (name "unconnected-(K1io-Pad4)") (class "Default")
      (node (ref "K1io") (pin "4") (pinfunction "4_4") (pintype "passive+no_connect"))
    )
    (net (code "65") (name "unconnected-(K2io-Pad4)") (class "Default")
      (node (ref "K2io") (pin "4") (pinfunction "4_4") (pintype "passive+no_connect"))
    )
    (net (code "66") (name "unconnected-(VD5io-Pad3)") (class "Default")
      (node (ref "VD5io") (pin "3") (pinfunction "3_3") (pintype "passive+no_connect"))
    )
    (net (code "67") (name "unconnected-(VD11io-Pad3)") (class "Default")
      (node (ref "VD11io") (pin "3") (pinfunction "3_3") (pintype "passive+no_connect"))
    )
    (net (code "68") (name "unconnected-(VD16io-Pad3)") (class "Default")
      (node (ref "VD16io") (pin "3") (pinfunction "3_3") (pintype "passive+no_connect"))
    )
  )
)
